# muxi_control.net
KiCad netlist of a schematic drawn in EAGLE
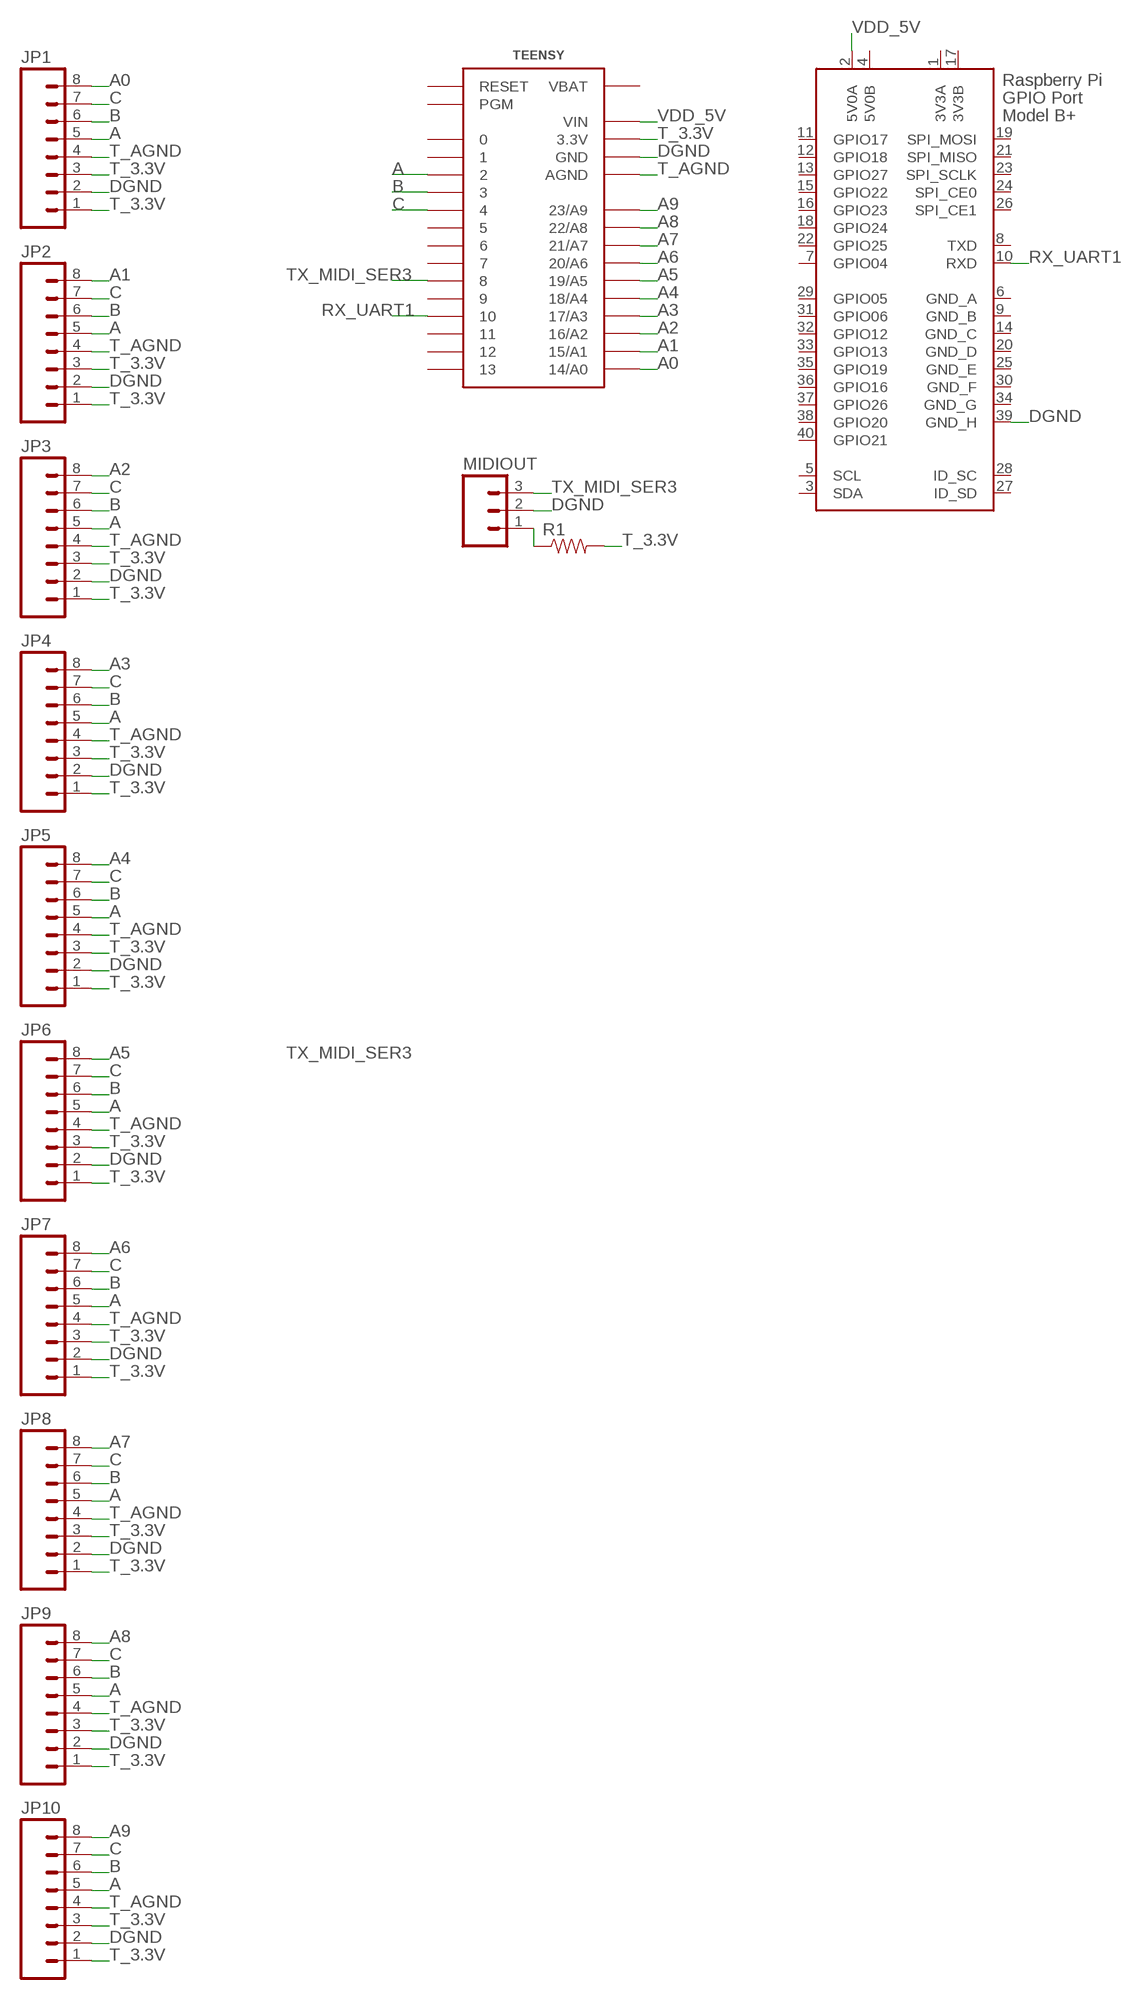
[diagram p0: schematic, sheet 1]

(export (version "E")
  (design (tool "Eeschema 10.0.6"))
  (components
    (comp (ref "JP1")
      (value "M081X08")
      (footprint "eagle-import:1X08")
      (libsource (lib "eagle-import") (part "M081X08"))
    )
    (comp (ref "JP2")
      (value "M081X08")
      (footprint "eagle-import:1X08")
      (libsource (lib "eagle-import") (part "M081X08"))
    )
    (comp (ref "JP3")
      (value "M081X08")
      (footprint "eagle-import:1X08")
      (libsource (lib "eagle-import") (part "M081X08"))
    )
    (comp (ref "JP4")
      (value "M081X08")
      (footprint "eagle-import:1X08")
      (libsource (lib "eagle-import") (part "M081X08"))
    )
    (comp (ref "JP5")
      (value "M081X08")
      (footprint "eagle-import:1X08")
      (libsource (lib "eagle-import") (part "M081X08"))
    )
    (comp (ref "JP6")
      (value "M081X08")
      (footprint "eagle-import:1X08")
      (libsource (lib "eagle-import") (part "M081X08"))
    )
    (comp (ref "JP7")
      (value "M081X08")
      (footprint "eagle-import:1X08")
      (libsource (lib "eagle-import") (part "M081X08"))
    )
    (comp (ref "JP8")
      (value "M081X08")
      (footprint "eagle-import:1X08")
      (libsource (lib "eagle-import") (part "M081X08"))
    )
    (comp (ref "JP9")
      (value "M081X08")
      (footprint "eagle-import:1X08")
      (libsource (lib "eagle-import") (part "M081X08"))
    )
    (comp (ref "JP10")
      (value "M081X08")
      (footprint "eagle-import:1X08")
      (libsource (lib "eagle-import") (part "M081X08"))
    )
    (comp (ref "MIDIOUT")
      (value "M03PTH")
      (footprint "eagle-import:1X03")
      (libsource (lib "eagle-import") (part "M03PTH"))
    )
    (comp (ref "R1")
      (value "RESISTORAXIAL-0.3")
      (footprint "eagle-import:AXIAL-0.3")
      (libsource (lib "eagle-import") (part "RESISTORAXIAL-0.3"))
    )
    (comp (ref "TEENSY")
      (value "TEENSY_3.0_BASIC")
      (footprint "eagle-import:TEENSY_3.0_BASIC")
      (libsource (lib "eagle-import") (part "TEENSY_3.0_BASIC"))
    )
    (comp (ref "X1")
      (value "RASPI_BOARD_B+#_H")
      (footprint "eagle-import:RASPI_BOARD_B+HAT")
      (libsource (lib "eagle-import") (part "RASPI_BOARD_B+#_H"))
    )
  )
  (nets
    (net (code "1") (name "/3V3A") (class "Default")
      (node (ref "X1") (pin "1") (pinfunction "3V3A_1") (pintype "power_in"))
    )
    (net (code "2") (name "/3V3B") (class "Default")
      (node (ref "X1") (pin "17") (pinfunction "3V3B_17") (pintype "power_in"))
    )
    (net (code "3") (name "/5V0B") (class "Default")
      (node (ref "X1") (pin "4") (pinfunction "5V0B_4") (pintype "power_in"))
    )
    (net (code "4") (name "/A") (class "Default")
      (node (ref "JP1") (pin "5") (pinfunction "5_5") (pintype "passive"))
      (node (ref "JP10") (pin "5") (pinfunction "5_5") (pintype "passive"))
      (node (ref "JP2") (pin "5") (pinfunction "5_5") (pintype "passive"))
      (node (ref "JP3") (pin "5") (pinfunction "5_5") (pintype "passive"))
      (node (ref "JP4") (pin "5") (pinfunction "5_5") (pintype "passive"))
      (node (ref "JP5") (pin "5") (pinfunction "5_5") (pintype "passive"))
      (node (ref "JP6") (pin "5") (pinfunction "5_5") (pintype "passive"))
      (node (ref "JP7") (pin "5") (pinfunction "5_5") (pintype "passive"))
      (node (ref "JP8") (pin "5") (pinfunction "5_5") (pintype "passive"))
      (node (ref "JP9") (pin "5") (pinfunction "5_5") (pintype "passive"))
      (node (ref "TEENSY") (pin "2") (pinfunction "2_2") (pintype "bidirectional"))
    )
    (net (code "5") (name "/A0") (class "Default")
      (node (ref "JP1") (pin "8") (pinfunction "8_8") (pintype "passive"))
      (node (ref "TEENSY") (pin "14/A0") (pinfunction "14/A0_14/A0") (pintype "bidirectional"))
    )
    (net (code "6") (name "/A1") (class "Default")
      (node (ref "JP2") (pin "8") (pinfunction "8_8") (pintype "passive"))
      (node (ref "TEENSY") (pin "15/A1") (pinfunction "15/A1_15/A1") (pintype "bidirectional"))
    )
    (net (code "7") (name "/A2") (class "Default")
      (node (ref "JP3") (pin "8") (pinfunction "8_8") (pintype "passive"))
      (node (ref "TEENSY") (pin "16/A2") (pinfunction "16/A2_16/A2") (pintype "bidirectional"))
    )
    (net (code "8") (name "/A3") (class "Default")
      (node (ref "JP4") (pin "8") (pinfunction "8_8") (pintype "passive"))
      (node (ref "TEENSY") (pin "17/A3") (pinfunction "17/A3_17/A3") (pintype "bidirectional"))
    )
    (net (code "9") (name "/A4") (class "Default")
      (node (ref "JP5") (pin "8") (pinfunction "8_8") (pintype "passive"))
      (node (ref "TEENSY") (pin "18/A4") (pinfunction "18/A4_18/A4") (pintype "bidirectional"))
    )
    (net (code "10") (name "/A5") (class "Default")
      (node (ref "JP6") (pin "8") (pinfunction "8_8") (pintype "passive"))
      (node (ref "TEENSY") (pin "19/A5") (pinfunction "19/A5_19/A5") (pintype "bidirectional"))
    )
    (net (code "11") (name "/A6") (class "Default")
      (node (ref "JP7") (pin "8") (pinfunction "8_8") (pintype "passive"))
      (node (ref "TEENSY") (pin "20/A6") (pinfunction "20/A6_20/A6") (pintype "bidirectional"))
    )
    (net (code "12") (name "/A7") (class "Default")
      (node (ref "JP8") (pin "8") (pinfunction "8_8") (pintype "passive"))
      (node (ref "TEENSY") (pin "21/A7") (pinfunction "21/A7_21/A7") (pintype "bidirectional"))
    )
    (net (code "13") (name "/A8") (class "Default")
      (node (ref "JP9") (pin "8") (pinfunction "8_8") (pintype "passive"))
      (node (ref "TEENSY") (pin "22/A8") (pinfunction "22/A8_22/A8") (pintype "bidirectional"))
    )
    (net (code "14") (name "/A9") (class "Default")
      (node (ref "JP10") (pin "8") (pinfunction "8_8") (pintype "passive"))
      (node (ref "TEENSY") (pin "23/A9") (pinfunction "23/A9_23/A9") (pintype "bidirectional"))
    )
    (net (code "15") (name "/B") (class "Default")
      (node (ref "JP1") (pin "6") (pinfunction "6_6") (pintype "passive"))
      (node (ref "JP10") (pin "6") (pinfunction "6_6") (pintype "passive"))
      (node (ref "JP2") (pin "6") (pinfunction "6_6") (pintype "passive"))
      (node (ref "JP3") (pin "6") (pinfunction "6_6") (pintype "passive"))
      (node (ref "JP4") (pin "6") (pinfunction "6_6") (pintype "passive"))
      (node (ref "JP5") (pin "6") (pinfunction "6_6") (pintype "passive"))
      (node (ref "JP6") (pin "6") (pinfunction "6_6") (pintype "passive"))
      (node (ref "JP7") (pin "6") (pinfunction "6_6") (pintype "passive"))
      (node (ref "JP8") (pin "6") (pinfunction "6_6") (pintype "passive"))
      (node (ref "JP9") (pin "6") (pinfunction "6_6") (pintype "passive"))
      (node (ref "TEENSY") (pin "3") (pinfunction "3_3") (pintype "bidirectional"))
    )
    (net (code "16") (name "/C") (class "Default")
      (node (ref "JP1") (pin "7") (pinfunction "7_7") (pintype "passive"))
      (node (ref "JP10") (pin "7") (pinfunction "7_7") (pintype "passive"))
      (node (ref "JP2") (pin "7") (pinfunction "7_7") (pintype "passive"))
      (node (ref "JP3") (pin "7") (pinfunction "7_7") (pintype "passive"))
      (node (ref "JP4") (pin "7") (pinfunction "7_7") (pintype "passive"))
      (node (ref "JP5") (pin "7") (pinfunction "7_7") (pintype "passive"))
      (node (ref "JP6") (pin "7") (pinfunction "7_7") (pintype "passive"))
      (node (ref "JP7") (pin "7") (pinfunction "7_7") (pintype "passive"))
      (node (ref "JP8") (pin "7") (pinfunction "7_7") (pintype "passive"))
      (node (ref "JP9") (pin "7") (pinfunction "7_7") (pintype "passive"))
      (node (ref "TEENSY") (pin "4") (pinfunction "4_4") (pintype "bidirectional"))
    )
    (net (code "17") (name "/DGND") (class "Default")
      (node (ref "JP1") (pin "2") (pinfunction "2_2") (pintype "passive"))
      (node (ref "JP10") (pin "2") (pinfunction "2_2") (pintype "passive"))
      (node (ref "JP2") (pin "2") (pinfunction "2_2") (pintype "passive"))
      (node (ref "JP3") (pin "2") (pinfunction "2_2") (pintype "passive"))
      (node (ref "JP4") (pin "2") (pinfunction "2_2") (pintype "passive"))
      (node (ref "JP5") (pin "2") (pinfunction "2_2") (pintype "passive"))
      (node (ref "JP6") (pin "2") (pinfunction "2_2") (pintype "passive"))
      (node (ref "JP7") (pin "2") (pinfunction "2_2") (pintype "passive"))
      (node (ref "JP8") (pin "2") (pinfunction "2_2") (pintype "passive"))
      (node (ref "JP9") (pin "2") (pinfunction "2_2") (pintype "passive"))
      (node (ref "MIDIOUT") (pin "2") (pinfunction "2_2") (pintype "passive"))
      (node (ref "TEENSY") (pin "GND") (pinfunction "GND_GND") (pintype "power_in"))
      (node (ref "TEENSY") (pin "GND1") (pinfunction "GND_GND1") (pintype "power_in"))
      (node (ref "X1") (pin "39") (pinfunction "GND_H_39") (pintype "power_in"))
    )
    (net (code "18") (name "/GND_A") (class "Default")
      (node (ref "X1") (pin "6") (pinfunction "GND_A_6") (pintype "power_in"))
    )
    (net (code "19") (name "/GND_B") (class "Default")
      (node (ref "X1") (pin "9") (pinfunction "GND_B_9") (pintype "power_in"))
    )
    (net (code "20") (name "/GND_C") (class "Default")
      (node (ref "X1") (pin "14") (pinfunction "GND_C_14") (pintype "power_in"))
    )
    (net (code "21") (name "/GND_D") (class "Default")
      (node (ref "X1") (pin "20") (pinfunction "GND_D_20") (pintype "power_in"))
    )
    (net (code "22") (name "/GND_E") (class "Default")
      (node (ref "X1") (pin "25") (pinfunction "GND_E_25") (pintype "power_in"))
    )
    (net (code "23") (name "/GND_F") (class "Default")
      (node (ref "X1") (pin "30") (pinfunction "GND_F_30") (pintype "power_in"))
    )
    (net (code "24") (name "/GND_G") (class "Default")
      (node (ref "X1") (pin "34") (pinfunction "GND_G_34") (pintype "power_in"))
    )
    (net (code "25") (name "/RX_UART1") (class "Default")
      (node (ref "TEENSY") (pin "10") (pinfunction "10_10") (pintype "bidirectional"))
      (node (ref "X1") (pin "10") (pinfunction "RXD_10") (pintype "bidirectional"))
    )
    (net (code "26") (name "/TX_MIDI_SER3") (class "Default")
      (node (ref "MIDIOUT") (pin "3") (pinfunction "3_3") (pintype "passive"))
      (node (ref "TEENSY") (pin "8") (pinfunction "8_8") (pintype "bidirectional"))
    )
    (net (code "27") (name "/T_3.3V") (class "Default")
      (node (ref "JP1") (pin "1") (pinfunction "1_1") (pintype "passive"))
      (node (ref "JP1") (pin "3") (pinfunction "3_3") (pintype "passive"))
      (node (ref "JP10") (pin "1") (pinfunction "1_1") (pintype "passive"))
      (node (ref "JP10") (pin "3") (pinfunction "3_3") (pintype "passive"))
      (node (ref "JP2") (pin "1") (pinfunction "1_1") (pintype "passive"))
      (node (ref "JP2") (pin "3") (pinfunction "3_3") (pintype "passive"))
      (node (ref "JP3") (pin "1") (pinfunction "1_1") (pintype "passive"))
      (node (ref "JP3") (pin "3") (pinfunction "3_3") (pintype "passive"))
      (node (ref "JP4") (pin "1") (pinfunction "1_1") (pintype "passive"))
      (node (ref "JP4") (pin "3") (pinfunction "3_3") (pintype "passive"))
      (node (ref "JP5") (pin "1") (pinfunction "1_1") (pintype "passive"))
      (node (ref "JP5") (pin "3") (pinfunction "3_3") (pintype "passive"))
      (node (ref "JP6") (pin "1") (pinfunction "1_1") (pintype "passive"))
      (node (ref "JP6") (pin "3") (pinfunction "3_3") (pintype "passive"))
      (node (ref "JP7") (pin "1") (pinfunction "1_1") (pintype "passive"))
      (node (ref "JP7") (pin "3") (pinfunction "3_3") (pintype "passive"))
      (node (ref "JP8") (pin "1") (pinfunction "1_1") (pintype "passive"))
      (node (ref "JP8") (pin "3") (pinfunction "3_3") (pintype "passive"))
      (node (ref "JP9") (pin "1") (pinfunction "1_1") (pintype "passive"))
      (node (ref "JP9") (pin "3") (pinfunction "3_3") (pintype "passive"))
      (node (ref "R1") (pin "P$2") (pinfunction "2_P$2") (pintype "passive"))
      (node (ref "TEENSY") (pin "3.3V") (pinfunction "3.3V_3.3V") (pintype "power_in"))
      (node (ref "TEENSY") (pin "3.3V1") (pinfunction "3.3V_3.3V1") (pintype "power_in"))
    )
    (net (code "28") (name "/T_AGND") (class "Default")
      (node (ref "JP1") (pin "4") (pinfunction "4_4") (pintype "passive"))
      (node (ref "JP10") (pin "4") (pinfunction "4_4") (pintype "passive"))
      (node (ref "JP2") (pin "4") (pinfunction "4_4") (pintype "passive"))
      (node (ref "JP3") (pin "4") (pinfunction "4_4") (pintype "passive"))
      (node (ref "JP4") (pin "4") (pinfunction "4_4") (pintype "passive"))
      (node (ref "JP5") (pin "4") (pinfunction "4_4") (pintype "passive"))
      (node (ref "JP6") (pin "4") (pinfunction "4_4") (pintype "passive"))
      (node (ref "JP7") (pin "4") (pinfunction "4_4") (pintype "passive"))
      (node (ref "JP8") (pin "4") (pinfunction "4_4") (pintype "passive"))
      (node (ref "JP9") (pin "4") (pinfunction "4_4") (pintype "passive"))
      (node (ref "TEENSY") (pin "AGND") (pinfunction "AGND_AGND") (pintype "power_in"))
    )
    (net (code "29") (name "/VBAT") (class "Default")
      (node (ref "TEENSY") (pin "VBAT") (pinfunction "VBAT_VBAT") (pintype "power_in"))
    )
    (net (code "30") (name "/VDD_5V") (class "Default")
      (node (ref "TEENSY") (pin "VIN") (pinfunction "VIN_VIN") (pintype "power_in"))
      (node (ref "X1") (pin "2") (pinfunction "5V0A_2") (pintype "power_in"))
    )
    (net (code "31") (name "Net-(R1-1)") (class "Default")
      (node (ref "MIDIOUT") (pin "1") (pinfunction "1_1") (pintype "passive"))
      (node (ref "R1") (pin "P$1") (pinfunction "1_P$1") (pintype "passive"))
    )
    (net (code "32") (name "unconnected-(TEENSY-Pad0)") (class "Default")
      (node (ref "TEENSY") (pin "0") (pinfunction "0_0") (pintype "bidirectional"))
    )
    (net (code "33") (name "unconnected-(TEENSY-Pad1)") (class "Default")
      (node (ref "TEENSY") (pin "1") (pinfunction "1_1") (pintype "bidirectional"))
    )
    (net (code "34") (name "unconnected-(TEENSY-Pad5)") (class "Default")
      (node (ref "TEENSY") (pin "5") (pinfunction "5_5") (pintype "bidirectional"))
    )
    (net (code "35") (name "unconnected-(TEENSY-Pad6)") (class "Default")
      (node (ref "TEENSY") (pin "6") (pinfunction "6_6") (pintype "bidirectional"))
    )
    (net (code "36") (name "unconnected-(TEENSY-Pad7)") (class "Default")
      (node (ref "TEENSY") (pin "7") (pinfunction "7_7") (pintype "bidirectional"))
    )
    (net (code "37") (name "unconnected-(TEENSY-Pad9)") (class "Default")
      (node (ref "TEENSY") (pin "9") (pinfunction "9_9") (pintype "bidirectional"))
    )
    (net (code "38") (name "unconnected-(TEENSY-Pad11)") (class "Default")
      (node (ref "TEENSY") (pin "11") (pinfunction "11_11") (pintype "bidirectional"))
    )
    (net (code "39") (name "unconnected-(TEENSY-Pad12)") (class "Default")
      (node (ref "TEENSY") (pin "12") (pinfunction "12_12") (pintype "bidirectional"))
    )
    (net (code "40") (name "unconnected-(TEENSY-Pad13)") (class "Default")
      (node (ref "TEENSY") (pin "13") (pinfunction "13_13") (pintype "bidirectional"))
    )
    (net (code "41") (name "unconnected-(TEENSY-PadPGM)") (class "Default")
      (node (ref "TEENSY") (pin "PGM") (pinfunction "PGM_PGM") (pintype "bidirectional"))
    )
    (net (code "42") (name "unconnected-(TEENSY-PadRESET)") (class "Default")
      (node (ref "TEENSY") (pin "RESET") (pinfunction "RESET_RESET") (pintype "bidirectional"))
    )
    (net (code "43") (name "unconnected-(X1-GPIO04-Pad7)") (class "Default")
      (node (ref "X1") (pin "7") (pinfunction "GPIO04_7") (pintype "bidirectional"))
    )
    (net (code "44") (name "unconnected-(X1-GPIO05-Pad29)") (class "Default")
      (node (ref "X1") (pin "29") (pinfunction "GPIO05_29") (pintype "no_connect"))
    )
    (net (code "45") (name "unconnected-(X1-GPIO06-Pad31)") (class "Default")
      (node (ref "X1") (pin "31") (pinfunction "GPIO06_31") (pintype "no_connect"))
    )
    (net (code "46") (name "unconnected-(X1-GPIO12-Pad32)") (class "Default")
      (node (ref "X1") (pin "32") (pinfunction "GPIO12_32") (pintype "no_connect"))
    )
    (net (code "47") (name "unconnected-(X1-GPIO13-Pad33)") (class "Default")
      (node (ref "X1") (pin "33") (pinfunction "GPIO13_33") (pintype "no_connect"))
    )
    (net (code "48") (name "unconnected-(X1-GPIO16-Pad36)") (class "Default")
      (node (ref "X1") (pin "36") (pinfunction "GPIO16_36") (pintype "no_connect"))
    )
    (net (code "49") (name "unconnected-(X1-GPIO17-Pad11)") (class "Default")
      (node (ref "X1") (pin "11") (pinfunction "GPIO17_11") (pintype "bidirectional"))
    )
    (net (code "50") (name "unconnected-(X1-GPIO18-Pad12)") (class "Default")
      (node (ref "X1") (pin "12") (pinfunction "GPIO18_12") (pintype "bidirectional"))
    )
    (net (code "51") (name "unconnected-(X1-GPIO19-Pad35)") (class "Default")
      (node (ref "X1") (pin "35") (pinfunction "GPIO19_35") (pintype "no_connect"))
    )
    (net (code "52") (name "unconnected-(X1-GPIO20-Pad38)") (class "Default")
      (node (ref "X1") (pin "38") (pinfunction "GPIO20_38") (pintype "no_connect"))
    )
    (net (code "53") (name "unconnected-(X1-GPIO21-Pad40)") (class "Default")
      (node (ref "X1") (pin "40") (pinfunction "GPIO21_40") (pintype "no_connect"))
    )
    (net (code "54") (name "unconnected-(X1-GPIO22-Pad15)") (class "Default")
      (node (ref "X1") (pin "15") (pinfunction "GPIO22_15") (pintype "bidirectional"))
    )
    (net (code "55") (name "unconnected-(X1-GPIO23-Pad16)") (class "Default")
      (node (ref "X1") (pin "16") (pinfunction "GPIO23_16") (pintype "bidirectional"))
    )
    (net (code "56") (name "unconnected-(X1-GPIO24-Pad18)") (class "Default")
      (node (ref "X1") (pin "18") (pinfunction "GPIO24_18") (pintype "bidirectional"))
    )
    (net (code "57") (name "unconnected-(X1-GPIO25-Pad22)") (class "Default")
      (node (ref "X1") (pin "22") (pinfunction "GPIO25_22") (pintype "bidirectional"))
    )
    (net (code "58") (name "unconnected-(X1-GPIO26-Pad37)") (class "Default")
      (node (ref "X1") (pin "37") (pinfunction "GPIO26_37") (pintype "no_connect"))
    )
    (net (code "59") (name "unconnected-(X1-GPIO27-Pad13)") (class "Default")
      (node (ref "X1") (pin "13") (pinfunction "GPIO27_13") (pintype "bidirectional"))
    )
    (net (code "60") (name "unconnected-(X1-ID_SC-Pad28)") (class "Default")
      (node (ref "X1") (pin "28") (pinfunction "ID_SC_28") (pintype "no_connect"))
    )
    (net (code "61") (name "unconnected-(X1-ID_SD-Pad27)") (class "Default")
      (node (ref "X1") (pin "27") (pinfunction "ID_SD_27") (pintype "no_connect"))
    )
    (net (code "62") (name "unconnected-(X1-SCL-Pad5)") (class "Default")
      (node (ref "X1") (pin "5") (pinfunction "SCL_5") (pintype "bidirectional"))
    )
    (net (code "63") (name "unconnected-(X1-SDA-Pad3)") (class "Default")
      (node (ref "X1") (pin "3") (pinfunction "SDA_3") (pintype "bidirectional"))
    )
    (net (code "64") (name "unconnected-(X1-SPI_CE0-Pad24)") (class "Default")
      (node (ref "X1") (pin "24") (pinfunction "SPI_CE0_24") (pintype "bidirectional"))
    )
    (net (code "65") (name "unconnected-(X1-SPI_CE1-Pad26)") (class "Default")
      (node (ref "X1") (pin "26") (pinfunction "SPI_CE1_26") (pintype "bidirectional"))
    )
    (net (code "66") (name "unconnected-(X1-SPI_MISO-Pad21)") (class "Default")
      (node (ref "X1") (pin "21") (pinfunction "SPI_MISO_21") (pintype "bidirectional"))
    )
    (net (code "67") (name "unconnected-(X1-SPI_MOSI-Pad19)") (class "Default")
      (node (ref "X1") (pin "19") (pinfunction "SPI_MOSI_19") (pintype "bidirectional"))
    )
    (net (code "68") (name "unconnected-(X1-SPI_SCLK-Pad23)") (class "Default")
      (node (ref "X1") (pin "23") (pinfunction "SPI_SCLK_23") (pintype "bidirectional"))
    )
    (net (code "69") (name "unconnected-(X1-TXD-Pad8)") (class "Default")
      (node (ref "X1") (pin "8") (pinfunction "TXD_8") (pintype "bidirectional"))
    )
  )
)
